# boardfix.net
KiCad netlist of a schematic drawn in EAGLE
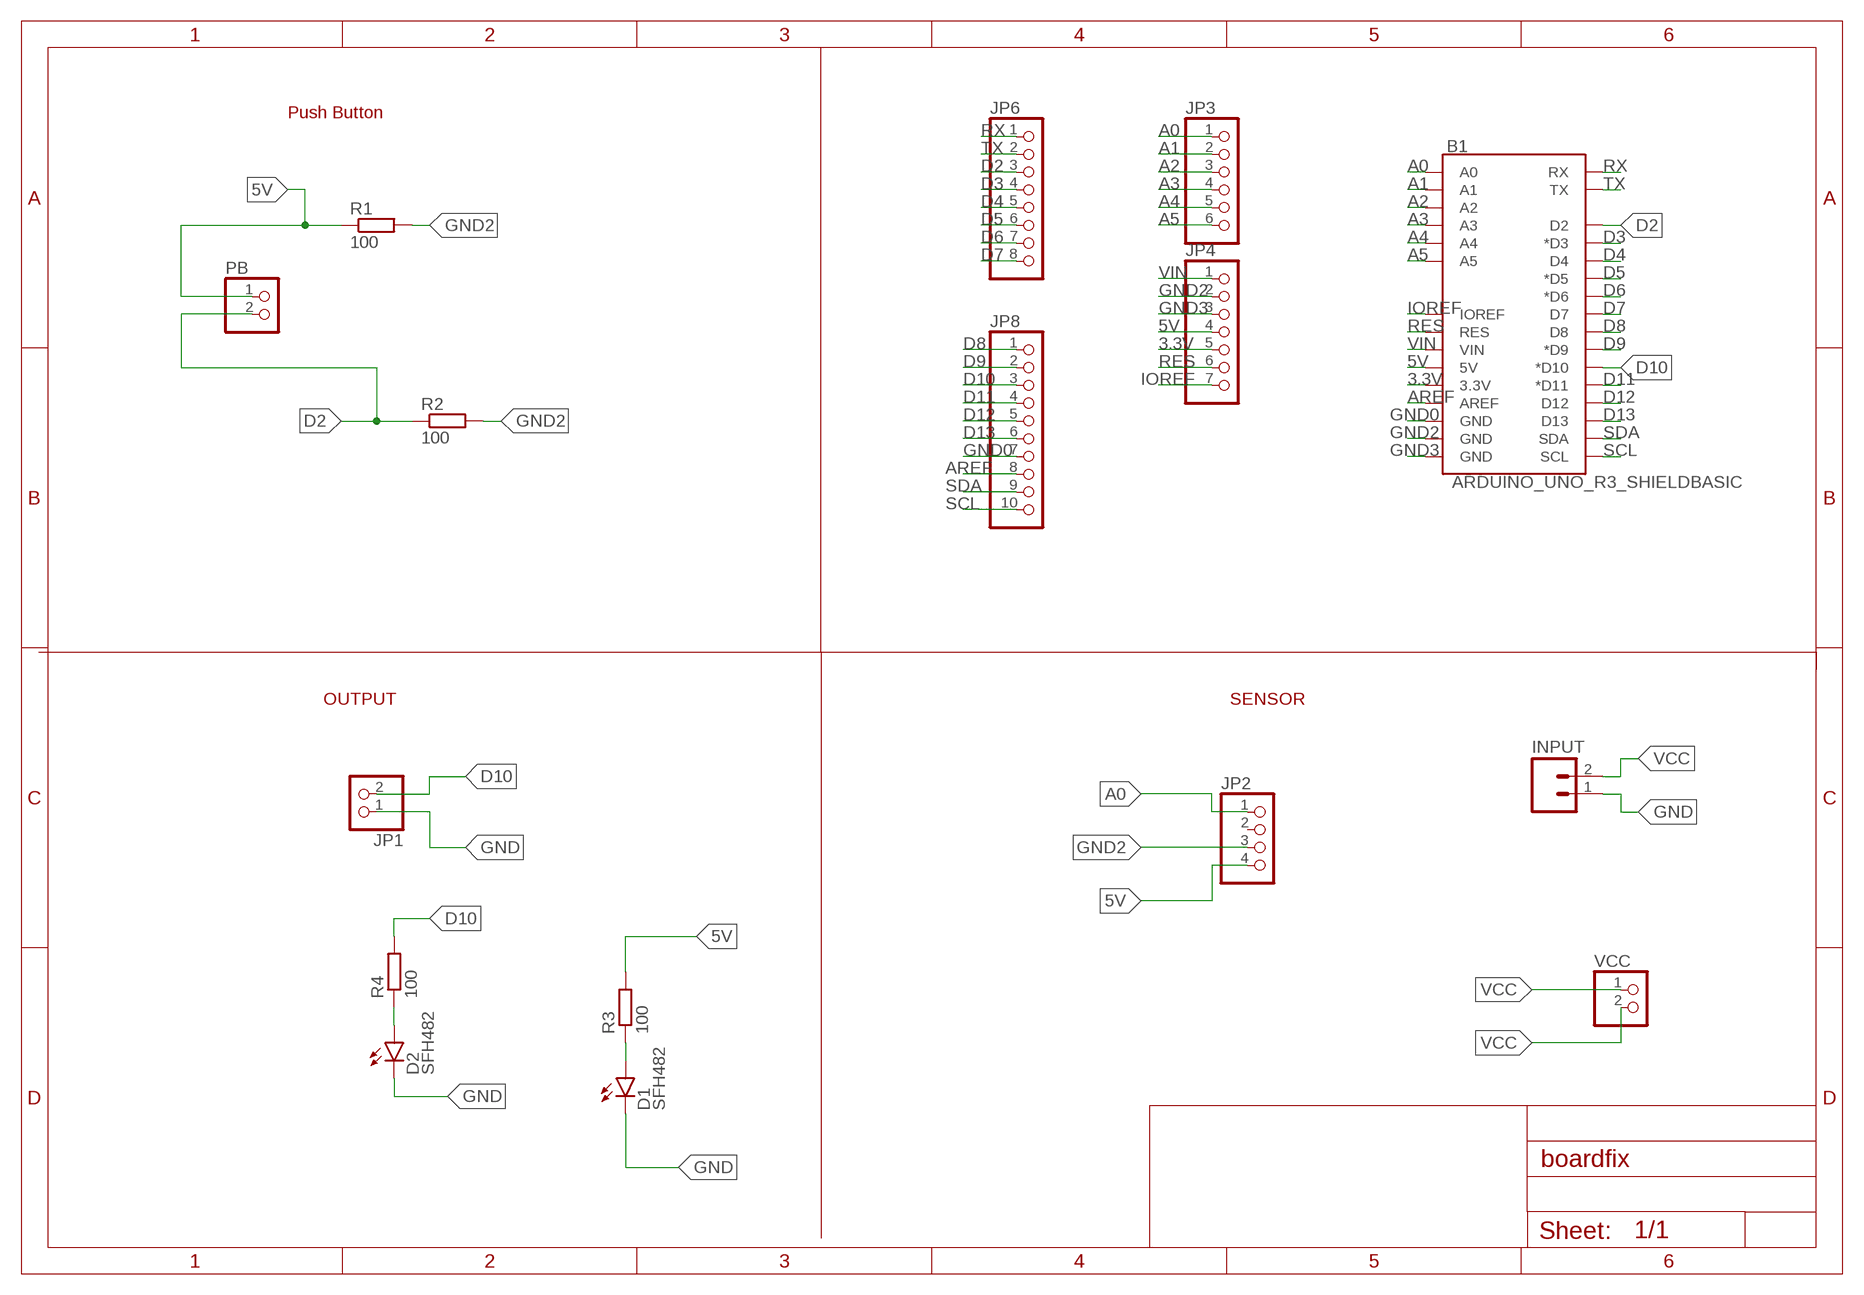
[diagram p0: schematic, sheet 1]

(export (version "E")
  (design (tool "Eeschema 10.0.6"))
  (components
    (comp (ref "B1")
      (value "ARDUINO_UNO_R3_SHIELDBASIC")
      (footprint "eagle-import:UNO_R3_SHIELD")
      (libsource (lib "eagle-import") (part "ARDUINO_UNO_R3_SHIELDBASIC"))
    )
    (comp (ref "D1")
      (value "SFH482")
      (footprint "eagle-import:SFH482")
      (libsource (lib "eagle-import") (part "SFH482"))
    )
    (comp (ref "D2")
      (value "SFH482")
      (footprint "eagle-import:SFH482")
      (libsource (lib "eagle-import") (part "SFH482"))
    )
    (comp (ref "INPUT")
      (value "M02")
      (footprint "eagle-import:02P")
      (libsource (lib "eagle-import") (part "M02"))
    )
    (comp (ref "JP1")
      (value "PINHD-1X2")
      (footprint "eagle-import:1X02")
      (libsource (lib "eagle-import") (part "PINHD-1X2"))
    )
    (comp (ref "JP2")
      (value "PINHD-1X4")
      (footprint "eagle-import:1X04")
      (libsource (lib "eagle-import") (part "PINHD-1X4"))
    )
    (comp (ref "JP3")
      (value "PINHD-1X6")
      (footprint "eagle-import:1X06")
      (libsource (lib "eagle-import") (part "PINHD-1X6"))
    )
    (comp (ref "JP4")
      (value "PINHD-1X7")
      (footprint "eagle-import:1X07")
      (libsource (lib "eagle-import") (part "PINHD-1X7"))
    )
    (comp (ref "JP6")
      (value "PINHD-1X8")
      (footprint "eagle-import:1X08")
      (libsource (lib "eagle-import") (part "PINHD-1X8"))
    )
    (comp (ref "JP8")
      (value "PINHD-1X10")
      (footprint "eagle-import:1X10")
      (libsource (lib "eagle-import") (part "PINHD-1X10"))
    )
    (comp (ref "PB")
      (value "PINHD-1X2")
      (footprint "eagle-import:1X02")
      (libsource (lib "eagle-import") (part "PINHD-1X2"))
    )
    (comp (ref "R1")
      (value "100")
      (footprint "eagle-import:0207_7")
      (libsource (lib "eagle-import") (part "R-EU_0207/7"))
    )
    (comp (ref "R2")
      (value "100")
      (footprint "eagle-import:0207_7")
      (libsource (lib "eagle-import") (part "R-EU_0207/7"))
    )
    (comp (ref "R3")
      (value "100")
      (footprint "eagle-import:0207_7")
      (libsource (lib "eagle-import") (part "R-EU_0207/7"))
    )
    (comp (ref "R4")
      (value "100")
      (footprint "eagle-import:0207_7")
      (libsource (lib "eagle-import") (part "R-EU_0207/7"))
    )
    (comp (ref "VCC")
      (value "PINHD-1X2")
      (footprint "eagle-import:1X02")
      (libsource (lib "eagle-import") (part "PINHD-1X2"))
    )
  )
  (nets
    (net (code "1") (name "/3.3V") (class "Default")
      (node (ref "B1") (pin "3.3V") (pinfunction "3.3V_3.3V") (pintype "bidirectional"))
      (node (ref "JP4") (pin "5") (pinfunction "5_5") (pintype "passive"))
    )
    (net (code "2") (name "/A1") (class "Default")
      (node (ref "B1") (pin "A1") (pinfunction "A1_A1") (pintype "bidirectional"))
      (node (ref "JP3") (pin "2") (pinfunction "2_2") (pintype "passive"))
    )
    (net (code "3") (name "/A2") (class "Default")
      (node (ref "B1") (pin "A2") (pinfunction "A2_A2") (pintype "bidirectional"))
      (node (ref "JP3") (pin "3") (pinfunction "3_3") (pintype "passive"))
    )
    (net (code "4") (name "/A3") (class "Default")
      (node (ref "B1") (pin "A3") (pinfunction "A3_A3") (pintype "bidirectional"))
      (node (ref "JP3") (pin "4") (pinfunction "4_4") (pintype "passive"))
    )
    (net (code "5") (name "/A4") (class "Default")
      (node (ref "B1") (pin "A4") (pinfunction "A4_A4") (pintype "bidirectional"))
      (node (ref "JP3") (pin "5") (pinfunction "5_5") (pintype "passive"))
    )
    (net (code "6") (name "/A5") (class "Default")
      (node (ref "B1") (pin "A5") (pinfunction "A5_A5") (pintype "bidirectional"))
      (node (ref "JP3") (pin "6") (pinfunction "6_6") (pintype "passive"))
    )
    (net (code "7") (name "/AREF") (class "Default")
      (node (ref "B1") (pin "AREF") (pinfunction "AREF_AREF") (pintype "bidirectional"))
      (node (ref "JP8") (pin "8") (pinfunction "8_8") (pintype "passive"))
    )
    (net (code "8") (name "/D3") (class "Default")
      (node (ref "B1") (pin "D3") (pinfunction "*D3_D3") (pintype "bidirectional"))
      (node (ref "JP6") (pin "4") (pinfunction "4_4") (pintype "passive"))
    )
    (net (code "9") (name "/D4") (class "Default")
      (node (ref "B1") (pin "D4") (pinfunction "D4_D4") (pintype "bidirectional"))
      (node (ref "JP6") (pin "5") (pinfunction "5_5") (pintype "passive"))
    )
    (net (code "10") (name "/D5") (class "Default")
      (node (ref "B1") (pin "D5") (pinfunction "*D5_D5") (pintype "bidirectional"))
      (node (ref "JP6") (pin "6") (pinfunction "6_6") (pintype "passive"))
    )
    (net (code "11") (name "/D6") (class "Default")
      (node (ref "B1") (pin "D6") (pinfunction "*D6_D6") (pintype "bidirectional"))
      (node (ref "JP6") (pin "7") (pinfunction "7_7") (pintype "passive"))
    )
    (net (code "12") (name "/D7") (class "Default")
      (node (ref "B1") (pin "D7") (pinfunction "D7_D7") (pintype "bidirectional"))
      (node (ref "JP6") (pin "8") (pinfunction "8_8") (pintype "passive"))
    )
    (net (code "13") (name "/D8") (class "Default")
      (node (ref "B1") (pin "D8") (pinfunction "D8_D8") (pintype "bidirectional"))
      (node (ref "JP8") (pin "1") (pinfunction "1_1") (pintype "passive"))
    )
    (net (code "14") (name "/D9") (class "Default")
      (node (ref "B1") (pin "D9") (pinfunction "*D9_D9") (pintype "bidirectional"))
      (node (ref "JP8") (pin "2") (pinfunction "2_2") (pintype "passive"))
    )
    (net (code "15") (name "/D11") (class "Default")
      (node (ref "B1") (pin "D11") (pinfunction "*D11_D11") (pintype "bidirectional"))
      (node (ref "JP8") (pin "4") (pinfunction "4_4") (pintype "passive"))
    )
    (net (code "16") (name "/D12") (class "Default")
      (node (ref "B1") (pin "D12") (pinfunction "D12_D12") (pintype "bidirectional"))
      (node (ref "JP8") (pin "5") (pinfunction "5_5") (pintype "passive"))
    )
    (net (code "17") (name "/D13") (class "Default")
      (node (ref "B1") (pin "D13") (pinfunction "D13_D13") (pintype "bidirectional"))
      (node (ref "JP8") (pin "6") (pinfunction "6_6") (pintype "passive"))
    )
    (net (code "18") (name "/GND0") (class "Default")
      (node (ref "B1") (pin "GND@2") (pinfunction "GND_GND@2") (pintype "bidirectional"))
      (node (ref "JP8") (pin "7") (pinfunction "7_7") (pintype "passive"))
    )
    (net (code "19") (name "/GND3") (class "Default")
      (node (ref "B1") (pin "GND@0") (pinfunction "GND_GND@0") (pintype "bidirectional"))
      (node (ref "JP4") (pin "3") (pinfunction "3_3") (pintype "passive"))
    )
    (net (code "20") (name "/IOREF") (class "Default")
      (node (ref "B1") (pin "IOREF") (pinfunction "IOREF_IOREF") (pintype "bidirectional"))
      (node (ref "JP4") (pin "7") (pinfunction "7_7") (pintype "passive"))
    )
    (net (code "21") (name "/RES") (class "Default")
      (node (ref "B1") (pin "RES") (pinfunction "RES_RES") (pintype "bidirectional"))
      (node (ref "JP4") (pin "6") (pinfunction "6_6") (pintype "passive"))
    )
    (net (code "22") (name "/RX") (class "Default")
      (node (ref "B1") (pin "RX") (pinfunction "RX_RX") (pintype "bidirectional"))
      (node (ref "JP6") (pin "1") (pinfunction "1_1") (pintype "passive"))
    )
    (net (code "23") (name "/SCL") (class "Default")
      (node (ref "B1") (pin "SCL") (pinfunction "SCL_SCL") (pintype "bidirectional"))
      (node (ref "JP8") (pin "10") (pinfunction "10_10") (pintype "passive"))
    )
    (net (code "24") (name "/SDA") (class "Default")
      (node (ref "B1") (pin "SDA") (pinfunction "SDA_SDA") (pintype "bidirectional"))
      (node (ref "JP8") (pin "9") (pinfunction "9_9") (pintype "passive"))
    )
    (net (code "25") (name "/TX") (class "Default")
      (node (ref "B1") (pin "TX") (pinfunction "TX_TX") (pintype "bidirectional"))
      (node (ref "JP6") (pin "2") (pinfunction "2_2") (pintype "passive"))
    )
    (net (code "26") (name "/VIN") (class "Default")
      (node (ref "B1") (pin "VIN") (pinfunction "VIN_VIN") (pintype "bidirectional"))
      (node (ref "JP4") (pin "1") (pinfunction "1_1") (pintype "passive"))
    )
    (net (code "27") (name "5V") (class "Default")
      (node (ref "B1") (pin "5V") (pinfunction "5V_5V") (pintype "bidirectional"))
      (node (ref "JP2") (pin "4") (pinfunction "4_4") (pintype "passive"))
      (node (ref "JP4") (pin "4") (pinfunction "4_4") (pintype "passive"))
      (node (ref "PB") (pin "1") (pinfunction "1_1") (pintype "passive"))
      (node (ref "R1") (pin "1") (pinfunction "1_1") (pintype "passive"))
      (node (ref "R3") (pin "2") (pinfunction "2_2") (pintype "passive"))
    )
    (net (code "28") (name "A0") (class "Default")
      (node (ref "B1") (pin "A0") (pinfunction "A0_A0") (pintype "bidirectional"))
      (node (ref "JP2") (pin "1") (pinfunction "1_1") (pintype "passive"))
      (node (ref "JP3") (pin "1") (pinfunction "1_1") (pintype "passive"))
    )
    (net (code "29") (name "D2") (class "Default")
      (node (ref "B1") (pin "D2") (pinfunction "D2_D2") (pintype "bidirectional"))
      (node (ref "JP6") (pin "3") (pinfunction "3_3") (pintype "passive"))
      (node (ref "PB") (pin "2") (pinfunction "2_2") (pintype "passive"))
      (node (ref "R2") (pin "1") (pinfunction "1_1") (pintype "passive"))
    )
    (net (code "30") (name "D10") (class "Default")
      (node (ref "B1") (pin "D10") (pinfunction "*D10_D10") (pintype "bidirectional"))
      (node (ref "JP1") (pin "2") (pinfunction "2_2") (pintype "passive"))
      (node (ref "JP8") (pin "3") (pinfunction "3_3") (pintype "passive"))
      (node (ref "R4") (pin "2") (pinfunction "2_2") (pintype "passive"))
    )
    (net (code "31") (name "GND") (class "Default")
      (node (ref "D1") (pin "K") (pinfunction "C_K") (pintype "passive"))
      (node (ref "D2") (pin "K") (pinfunction "C_K") (pintype "passive"))
      (node (ref "INPUT") (pin "1") (pinfunction "1_1") (pintype "passive"))
      (node (ref "JP1") (pin "1") (pinfunction "1_1") (pintype "passive"))
    )
    (net (code "32") (name "GND2") (class "Default")
      (node (ref "B1") (pin "GND@1") (pinfunction "GND_GND@1") (pintype "bidirectional"))
      (node (ref "JP2") (pin "3") (pinfunction "3_3") (pintype "passive"))
      (node (ref "JP4") (pin "2") (pinfunction "2_2") (pintype "passive"))
      (node (ref "R1") (pin "2") (pinfunction "2_2") (pintype "passive"))
      (node (ref "R2") (pin "2") (pinfunction "2_2") (pintype "passive"))
    )
    (net (code "33") (name "Net-(D1-PadA)") (class "Default")
      (node (ref "D1") (pin "A") (pinfunction "A_A") (pintype "passive"))
      (node (ref "R3") (pin "1") (pinfunction "1_1") (pintype "passive"))
    )
    (net (code "34") (name "Net-(D2-PadA)") (class "Default")
      (node (ref "D2") (pin "A") (pinfunction "A_A") (pintype "passive"))
      (node (ref "R4") (pin "1") (pinfunction "1_1") (pintype "passive"))
    )
    (net (code "35") (name "VCC") (class "Default")
      (node (ref "INPUT") (pin "2") (pinfunction "2_2") (pintype "passive"))
      (node (ref "VCC") (pin "1") (pinfunction "1_1") (pintype "passive"))
      (node (ref "VCC") (pin "2") (pinfunction "2_2") (pintype "passive"))
    )
    (net (code "36") (name "unconnected-(JP2-Pad2)") (class "Default")
      (node (ref "JP2") (pin "2") (pinfunction "2_2") (pintype "passive"))
    )
  )
)
